# AfternoonCape_RevA1_TImux.net
KiCad netlist of a schematic drawn in Altium Designer
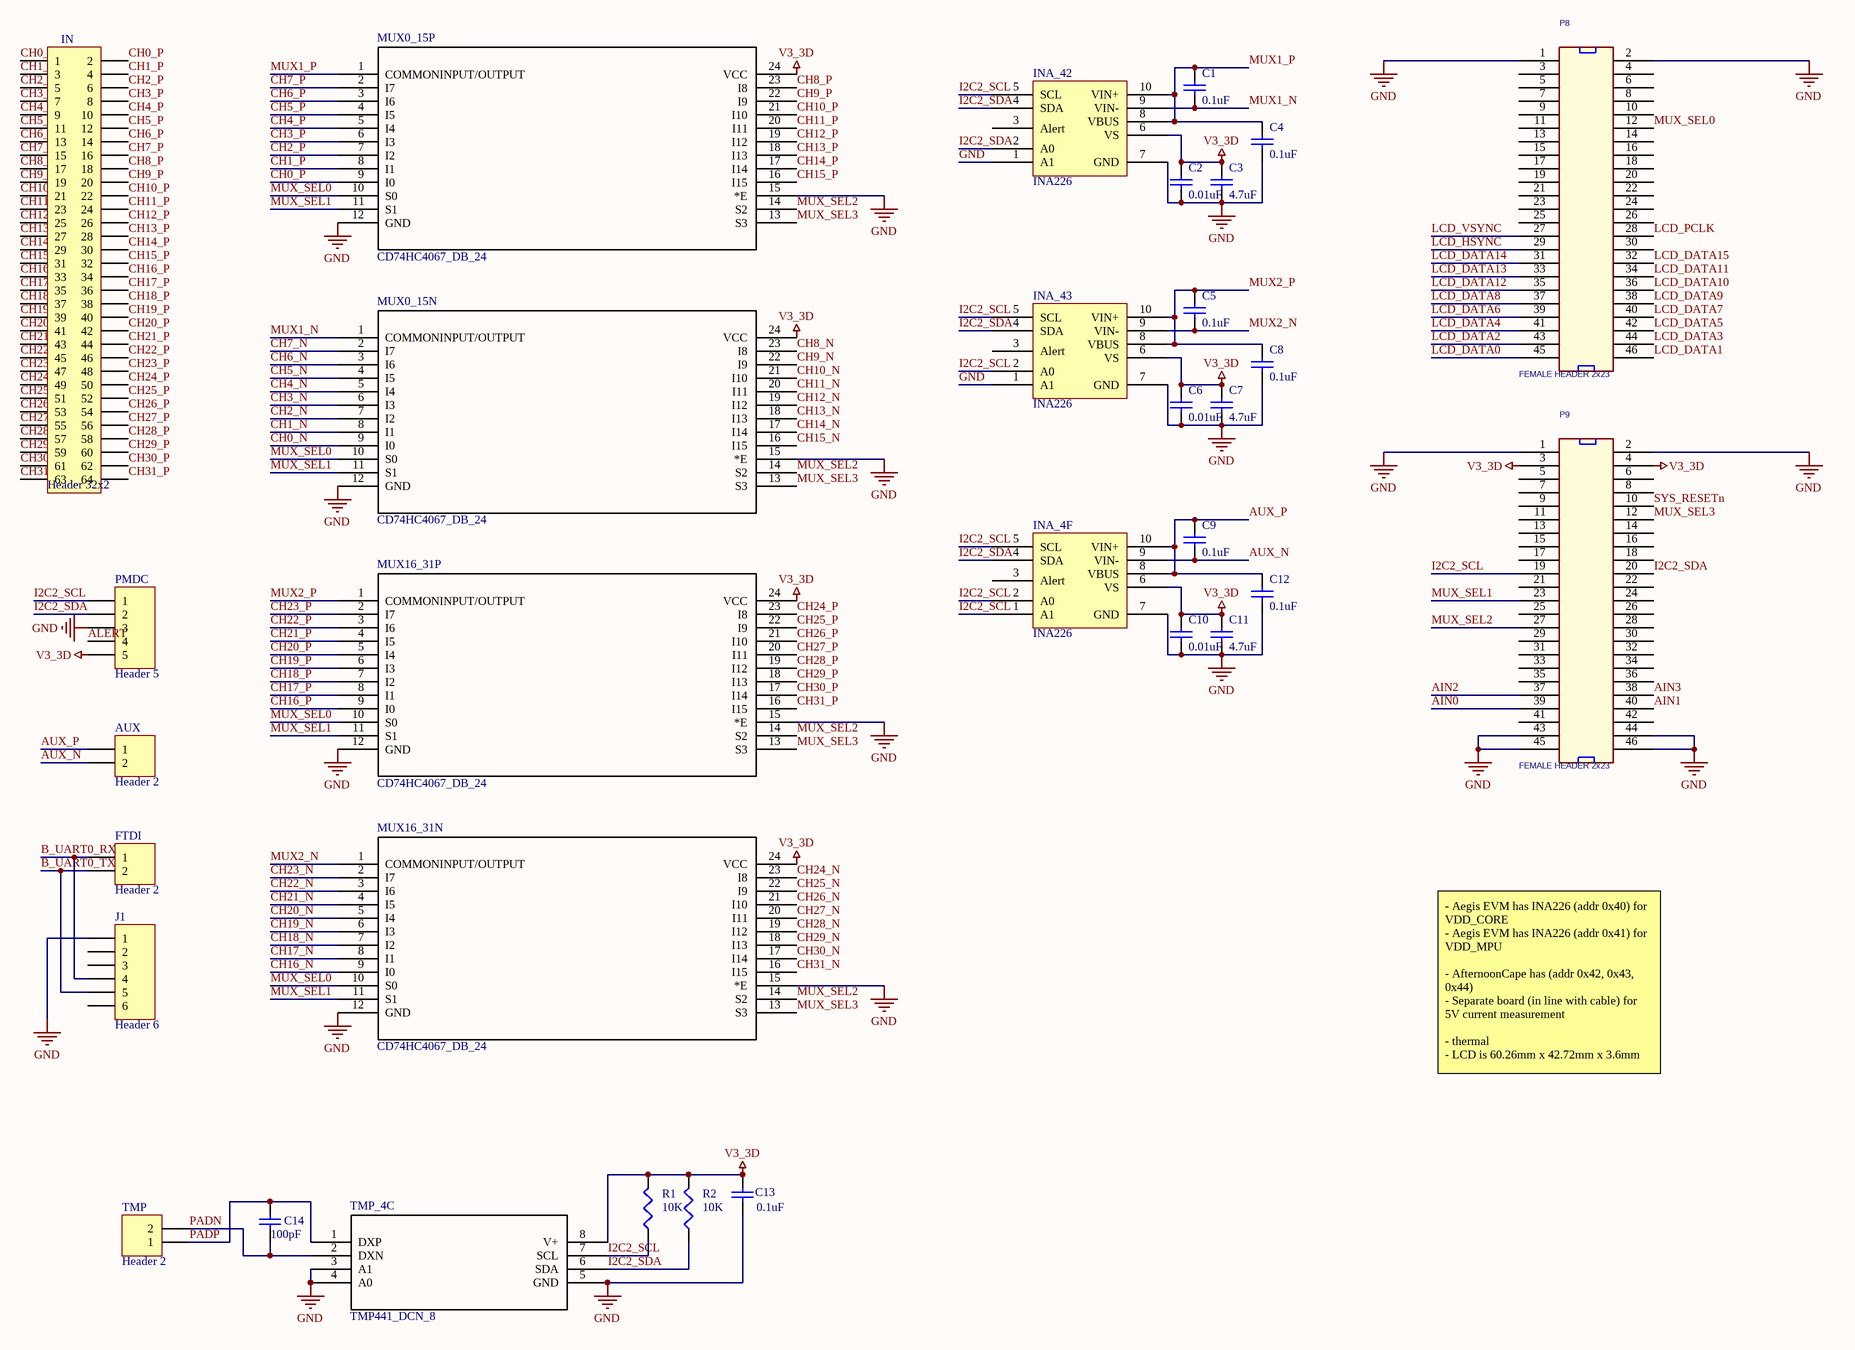
[diagram p0: AfternoonCape_RevA1_TImux.SchDoc]

(export (version "E")
  (design (tool "Eeschema 10.0.6"))
  (components
    (comp (ref "AUX")
      (value "Header 2")
      (footprint "HDR1X2")
      (description "Header, 2-Pin")
      (fields (field (name "PUBLISHER") "Altium Limited"))
      (libsource (lib "Miscellaneous Connectors") (part "Header 2"))
    )
    (comp (ref "C1")
      (value "0.1uF")
      (footprint "0402")
      (description "Capacitor (Semiconductor SIM Model)")
      (fields (field (name "Comment") "Cap Semi") (field (name "PUBLISHER") "Altium Limited"))
      (libsource (lib "Miscellaneous Devices") (part "Cap Semi"))
    )
    (comp (ref "C2")
      (value "0.01uF")
      (footprint "0402")
      (description "Capacitor (Semiconductor SIM Model)")
      (fields (field (name "Comment") "Cap Semi") (field (name "PUBLISHER") "Altium Limited"))
      (libsource (lib "Miscellaneous Devices") (part "Cap Semi"))
    )
    (comp (ref "C3")
      (value "4.7uF")
      (footprint "0402")
      (description "Capacitor (Semiconductor SIM Model)")
      (fields (field (name "Comment") "Cap Semi") (field (name "PUBLISHER") "Altium Limited"))
      (libsource (lib "Miscellaneous Devices") (part "Cap Semi"))
    )
    (comp (ref "C4")
      (value "0.1uF")
      (footprint "0402")
      (description "Capacitor (Semiconductor SIM Model)")
      (fields (field (name "Comment") "Cap Semi") (field (name "PUBLISHER") "Altium Limited"))
      (libsource (lib "Miscellaneous Devices") (part "Cap Semi"))
    )
    (comp (ref "C5")
      (value "0.1uF")
      (footprint "0402")
      (description "Capacitor (Semiconductor SIM Model)")
      (fields (field (name "Comment") "Cap Semi") (field (name "PUBLISHER") "Altium Limited"))
      (libsource (lib "Miscellaneous Devices") (part "Cap Semi"))
    )
    (comp (ref "C6")
      (value "0.01uF")
      (footprint "0402")
      (description "Capacitor (Semiconductor SIM Model)")
      (fields (field (name "Comment") "Cap Semi") (field (name "PUBLISHER") "Altium Limited"))
      (libsource (lib "Miscellaneous Devices") (part "Cap Semi"))
    )
    (comp (ref "C7")
      (value "4.7uF")
      (footprint "0402")
      (description "Capacitor (Semiconductor SIM Model)")
      (fields (field (name "Comment") "Cap Semi") (field (name "PUBLISHER") "Altium Limited"))
      (libsource (lib "Miscellaneous Devices") (part "Cap Semi"))
    )
    (comp (ref "C8")
      (value "0.1uF")
      (footprint "0402")
      (description "Capacitor (Semiconductor SIM Model)")
      (fields (field (name "Comment") "Cap Semi") (field (name "PUBLISHER") "Altium Limited"))
      (libsource (lib "Miscellaneous Devices") (part "Cap Semi"))
    )
    (comp (ref "C9")
      (value "0.1uF")
      (footprint "0402")
      (description "Capacitor (Semiconductor SIM Model)")
      (fields (field (name "Comment") "Cap Semi") (field (name "PUBLISHER") "Altium Limited"))
      (libsource (lib "Miscellaneous Devices") (part "Cap Semi"))
    )
    (comp (ref "C10")
      (value "0.01uF")
      (footprint "0402")
      (description "Capacitor (Semiconductor SIM Model)")
      (fields (field (name "Comment") "Cap Semi") (field (name "PUBLISHER") "Altium Limited"))
      (libsource (lib "Miscellaneous Devices") (part "Cap Semi"))
    )
    (comp (ref "C11")
      (value "4.7uF")
      (footprint "0402")
      (description "Capacitor (Semiconductor SIM Model)")
      (fields (field (name "Comment") "Cap Semi") (field (name "PUBLISHER") "Altium Limited"))
      (libsource (lib "Miscellaneous Devices") (part "Cap Semi"))
    )
    (comp (ref "C12")
      (value "0.1uF")
      (footprint "0402")
      (description "Capacitor (Semiconductor SIM Model)")
      (fields (field (name "Comment") "Cap Semi") (field (name "PUBLISHER") "Altium Limited"))
      (libsource (lib "Miscellaneous Devices") (part "Cap Semi"))
    )
    (comp (ref "C13")
      (value "0.1uF")
      (footprint "0402")
      (description "Capacitor (Semiconductor SIM Model)")
      (fields (field (name "Comment") "Cap Semi") (field (name "PUBLISHER") "Altium Limited"))
      (libsource (lib "Miscellaneous Devices") (part "Cap Semi"))
    )
    (comp (ref "C14")
      (value "100pF")
      (footprint "0402")
      (description "Capacitor (Semiconductor SIM Model)")
      (fields (field (name "Comment") "Cap Semi") (field (name "PUBLISHER") "Altium Limited"))
      (libsource (lib "Miscellaneous Devices") (part "Cap Semi"))
    )
    (comp (ref "FTDI")
      (value "Header 2")
      (footprint "HDR1X2")
      (description "Header, 2-Pin")
      (fields (field (name "PUBLISHER") "Altium Limited"))
      (libsource (lib "Miscellaneous Connectors") (part "Header 2"))
    )
    (comp (ref "IN")
      (value "Header 32x2")
      (footprint "HDR2x32")
      (description "Header, 32-Pin, Dual row")
      (libsource (lib "Miscellaneous Connectors") (part "Header 32x2"))
    )
    (comp (ref "INA_4F") (value "INA226") (footprint "DGS10") (libsource (lib "INA226") (part "INA226")))
    (comp (ref "INA_42") (value "INA226") (footprint "DGS10") (libsource (lib "INA226") (part "INA226")))
    (comp (ref "INA_43") (value "INA226") (footprint "DGS10") (libsource (lib "INA226") (part "INA226")))
    (comp (ref "J1")
      (value "Header 6")
      (footprint "HDR1X6")
      (description "6-pin female header, long legs for FTDI-USB cable")
      (fields (field (name "PUBLISHER") "Altium Limited"))
      (libsource (lib "Miscellaneous Connectors") (part "Header 6"))
    )
    (comp (ref "MUX0_15N")
      (value "CD74HC4067_DB_24")
      (footprint "DB24")
      (description "Imported")
      (fields
        (field (name "MANUFACTURER") "Texas Instruments")
        (field (name "GENERIC_PART_NUMBER") "CD74HC4067")
      )
      (libsource (lib "CD74HC4067_DB") (part "CD74HC4067_DB_24"))
    )
    (comp (ref "MUX0_15P")
      (value "CD74HC4067_DB_24")
      (footprint "DB24")
      (description "Imported")
      (fields
        (field (name "MANUFACTURER") "Texas Instruments")
        (field (name "GENERIC_PART_NUMBER") "CD74HC4067")
      )
      (libsource (lib "CD74HC4067_DB") (part "CD74HC4067_DB_24"))
    )
    (comp (ref "MUX16_31N")
      (value "CD74HC4067_DB_24")
      (footprint "DB24")
      (description "Imported")
      (fields
        (field (name "MANUFACTURER") "Texas Instruments")
        (field (name "GENERIC_PART_NUMBER") "CD74HC4067")
      )
      (libsource (lib "CD74HC4067_DB") (part "CD74HC4067_DB_24"))
    )
    (comp (ref "MUX16_31P")
      (value "CD74HC4067_DB_24")
      (footprint "DB24")
      (description "Imported")
      (fields
        (field (name "MANUFACTURER") "Texas Instruments")
        (field (name "GENERIC_PART_NUMBER") "CD74HC4067")
      )
      (libsource (lib "CD74HC4067_DB") (part "CD74HC4067_DB_24"))
    )
    (comp (ref "P8")
      (value "FEMALE HEADER 2x23")
      (description "CONN HEADER FMAL 46PS.1\" DL GOLD")
      (fields
        (field (name "MANUFACTURER") "Sullins Connector Solutions")
        (field (name "MANUFACTURER PART NUMBER") "PPPC232LFBN-RC")
      )
      (libsource (lib "BEAGLEBONEBLACK_REV A5B") (part "HDR_46_F_2_0.1_0.1"))
    )
    (comp (ref "P9")
      (value "FEMALE HEADER 2x23")
      (description "CONN HEADER FMAL 46PS.1\" DL GOLD")
      (fields
        (field (name "MANUFACTURER") "Sullins Connector Solutions")
        (field (name "MANUFACTURER PART NUMBER") "PPPC232LFBN-RC")
      )
      (libsource (lib "BEAGLEBONEBLACK_REV A5B") (part "HDR_46_F_2_0.1_0.1"))
    )
    (comp (ref "PMDC")
      (value "Header 5")
      (footprint "HDR1X5")
      (description "Header, 5-Pin")
      (fields (field (name "PUBLISHER") "Altium Limited"))
      (libsource (lib "Miscellaneous Connectors") (part "Header 5"))
    )
    (comp (ref "R1")
      (value "10K")
      (footprint "0402")
      (description "Resistor")
      (fields (field (name "Comment") "Res3") (field (name "PUBLISHER") "Altium Limited"))
      (libsource (lib "Miscellaneous Devices") (part "Res3"))
    )
    (comp (ref "R2")
      (value "10K")
      (footprint "0402")
      (description "Resistor")
      (fields (field (name "Comment") "Res3") (field (name "PUBLISHER") "Altium Limited"))
      (libsource (lib "Miscellaneous Devices") (part "Res3"))
    )
    (comp (ref "TMP")
      (value "Header 2")
      (footprint "HDR1X2")
      (description "Header, 2-Pin")
      (fields (field (name "PUBLISHER") "Altium Limited"))
      (libsource (lib "") (part "Header 2_1"))
    )
    (comp (ref "TMP_4C")
      (value "TMP441_DCN_8")
      (footprint "TMP441:DCN8-L")
      (description "Imported")
      (fields
        (field (name "MANUFACTURER_PART_NUMBER") "tmp441_dcn_8")
        (field (name "GENERIC_PART_NUMBER") "TMP441")
      )
      (libsource (lib "TMP441") (part "TMP441_DCN_8"))
    )
  )
  (nets
    (net (code "1") (name "/AIN0") (class "Default")
      (node (ref "P9") (pin "39") (pinfunction "20_39") (pintype "passive"))
    )
    (net (code "2") (name "/AIN1") (class "Default")
      (node (ref "P9") (pin "40") (pinfunction "45_40") (pintype "passive"))
    )
    (net (code "3") (name "/AIN2") (class "Default")
      (node (ref "P9") (pin "37") (pinfunction "19_37") (pintype "passive"))
    )
    (net (code "4") (name "/AIN3") (class "Default")
      (node (ref "P9") (pin "38") (pinfunction "44_38") (pintype "passive"))
    )
    (net (code "5") (name "/ALERT") (class "Default")
      (node (ref "PMDC") (pin "4") (pinfunction "4_4") (pintype "passive"))
    )
    (net (code "6") (name "/AUX_N") (class "Default")
      (node (ref "AUX") (pin "2") (pinfunction "2_2") (pintype "passive"))
      (node (ref "C9") (pin "1") (pinfunction "1_1") (pintype "passive"))
      (node (ref "INA_4F") (pin "9") (pinfunction "VIN-_9") (pintype "passive"))
    )
    (net (code "7") (name "/AUX_P") (class "Default")
      (node (ref "AUX") (pin "1") (pinfunction "1_1") (pintype "passive"))
      (node (ref "C12") (pin "2") (pinfunction "2_2") (pintype "passive"))
      (node (ref "C9") (pin "2") (pinfunction "2_2") (pintype "passive"))
      (node (ref "INA_4F") (pin "10") (pinfunction "VIN+_10") (pintype "passive"))
      (node (ref "INA_4F") (pin "8") (pinfunction "VBUS_8") (pintype "passive"))
    )
    (net (code "8") (name "/B_UART0_RX") (class "Default")
      (node (ref "FTDI") (pin "1") (pinfunction "1_1") (pintype "passive"))
      (node (ref "J1") (pin "4") (pinfunction "4_4") (pintype "passive"))
    )
    (net (code "9") (name "/B_UART0_TX") (class "Default")
      (node (ref "FTDI") (pin "2") (pinfunction "2_2") (pintype "passive"))
      (node (ref "J1") (pin "5") (pinfunction "5_5") (pintype "passive"))
    )
    (net (code "10") (name "/CH0_N") (class "Default")
      (node (ref "IN") (pin "1") (pinfunction "1_1") (pintype "passive"))
      (node (ref "MUX0_15N") (pin "9") (pinfunction "I0_9") (pintype "passive"))
    )
    (net (code "11") (name "/CH0_P") (class "Default")
      (node (ref "IN") (pin "2") (pinfunction "2_2") (pintype "passive"))
      (node (ref "MUX0_15P") (pin "9") (pinfunction "I0_9") (pintype "passive"))
    )
    (net (code "12") (name "/CH1_N") (class "Default")
      (node (ref "IN") (pin "3") (pinfunction "3_3") (pintype "passive"))
      (node (ref "MUX0_15N") (pin "8") (pinfunction "I1_8") (pintype "passive"))
    )
    (net (code "13") (name "/CH1_P") (class "Default")
      (node (ref "IN") (pin "4") (pinfunction "4_4") (pintype "passive"))
      (node (ref "MUX0_15P") (pin "8") (pinfunction "I1_8") (pintype "passive"))
    )
    (net (code "14") (name "/CH2_N") (class "Default")
      (node (ref "IN") (pin "5") (pinfunction "5_5") (pintype "passive"))
      (node (ref "MUX0_15N") (pin "7") (pinfunction "I2_7") (pintype "passive"))
    )
    (net (code "15") (name "/CH2_P") (class "Default")
      (node (ref "IN") (pin "6") (pinfunction "6_6") (pintype "passive"))
      (node (ref "MUX0_15P") (pin "7") (pinfunction "I2_7") (pintype "passive"))
    )
    (net (code "16") (name "/CH3_N") (class "Default")
      (node (ref "IN") (pin "7") (pinfunction "7_7") (pintype "passive"))
      (node (ref "MUX0_15N") (pin "6") (pinfunction "I3_6") (pintype "passive"))
    )
    (net (code "17") (name "/CH3_P") (class "Default")
      (node (ref "IN") (pin "8") (pinfunction "8_8") (pintype "passive"))
      (node (ref "MUX0_15P") (pin "6") (pinfunction "I3_6") (pintype "passive"))
    )
    (net (code "18") (name "/CH4_N") (class "Default")
      (node (ref "IN") (pin "9") (pinfunction "9_9") (pintype "passive"))
      (node (ref "MUX0_15N") (pin "5") (pinfunction "I4_5") (pintype "passive"))
    )
    (net (code "19") (name "/CH4_P") (class "Default")
      (node (ref "IN") (pin "10") (pinfunction "10_10") (pintype "passive"))
      (node (ref "MUX0_15P") (pin "5") (pinfunction "I4_5") (pintype "passive"))
    )
    (net (code "20") (name "/CH5_N") (class "Default")
      (node (ref "IN") (pin "11") (pinfunction "11_11") (pintype "passive"))
      (node (ref "MUX0_15N") (pin "4") (pinfunction "I5_4") (pintype "passive"))
    )
    (net (code "21") (name "/CH5_P") (class "Default")
      (node (ref "IN") (pin "12") (pinfunction "12_12") (pintype "passive"))
      (node (ref "MUX0_15P") (pin "4") (pinfunction "I5_4") (pintype "passive"))
    )
    (net (code "22") (name "/CH6_N") (class "Default")
      (node (ref "IN") (pin "13") (pinfunction "13_13") (pintype "passive"))
      (node (ref "MUX0_15N") (pin "3") (pinfunction "I6_3") (pintype "passive"))
    )
    (net (code "23") (name "/CH6_P") (class "Default")
      (node (ref "IN") (pin "14") (pinfunction "14_14") (pintype "passive"))
      (node (ref "MUX0_15P") (pin "3") (pinfunction "I6_3") (pintype "passive"))
    )
    (net (code "24") (name "/CH7_N") (class "Default")
      (node (ref "IN") (pin "15") (pinfunction "15_15") (pintype "passive"))
      (node (ref "MUX0_15N") (pin "2") (pinfunction "I7_2") (pintype "passive"))
    )
    (net (code "25") (name "/CH7_P") (class "Default")
      (node (ref "IN") (pin "16") (pinfunction "16_16") (pintype "passive"))
      (node (ref "MUX0_15P") (pin "2") (pinfunction "I7_2") (pintype "passive"))
    )
    (net (code "26") (name "/CH8_N") (class "Default")
      (node (ref "IN") (pin "17") (pinfunction "17_17") (pintype "passive"))
      (node (ref "MUX0_15N") (pin "23") (pinfunction "I8_23") (pintype "passive"))
    )
    (net (code "27") (name "/CH8_P") (class "Default")
      (node (ref "IN") (pin "18") (pinfunction "18_18") (pintype "passive"))
      (node (ref "MUX0_15P") (pin "23") (pinfunction "I8_23") (pintype "passive"))
    )
    (net (code "28") (name "/CH9_N") (class "Default")
      (node (ref "IN") (pin "19") (pinfunction "19_19") (pintype "passive"))
      (node (ref "MUX0_15N") (pin "22") (pinfunction "I9_22") (pintype "passive"))
    )
    (net (code "29") (name "/CH9_P") (class "Default")
      (node (ref "IN") (pin "20") (pinfunction "20_20") (pintype "passive"))
      (node (ref "MUX0_15P") (pin "22") (pinfunction "I9_22") (pintype "passive"))
    )
    (net (code "30") (name "/CH10_N") (class "Default")
      (node (ref "IN") (pin "21") (pinfunction "21_21") (pintype "passive"))
      (node (ref "MUX0_15N") (pin "21") (pinfunction "I10_21") (pintype "passive"))
    )
    (net (code "31") (name "/CH10_P") (class "Default")
      (node (ref "IN") (pin "22") (pinfunction "22_22") (pintype "passive"))
      (node (ref "MUX0_15P") (pin "21") (pinfunction "I10_21") (pintype "passive"))
    )
    (net (code "32") (name "/CH11_N") (class "Default")
      (node (ref "IN") (pin "23") (pinfunction "23_23") (pintype "passive"))
      (node (ref "MUX0_15N") (pin "20") (pinfunction "I11_20") (pintype "passive"))
    )
    (net (code "33") (name "/CH11_P") (class "Default")
      (node (ref "IN") (pin "24") (pinfunction "24_24") (pintype "passive"))
      (node (ref "MUX0_15P") (pin "20") (pinfunction "I11_20") (pintype "passive"))
    )
    (net (code "34") (name "/CH12_N") (class "Default")
      (node (ref "IN") (pin "25") (pinfunction "25_25") (pintype "passive"))
      (node (ref "MUX0_15N") (pin "19") (pinfunction "I12_19") (pintype "passive"))
    )
    (net (code "35") (name "/CH12_P") (class "Default")
      (node (ref "IN") (pin "26") (pinfunction "26_26") (pintype "passive"))
      (node (ref "MUX0_15P") (pin "19") (pinfunction "I12_19") (pintype "passive"))
    )
    (net (code "36") (name "/CH13_N") (class "Default")
      (node (ref "IN") (pin "27") (pinfunction "27_27") (pintype "passive"))
      (node (ref "MUX0_15N") (pin "18") (pinfunction "I13_18") (pintype "passive"))
    )
    (net (code "37") (name "/CH13_P") (class "Default")
      (node (ref "IN") (pin "28") (pinfunction "28_28") (pintype "passive"))
      (node (ref "MUX0_15P") (pin "18") (pinfunction "I13_18") (pintype "passive"))
    )
    (net (code "38") (name "/CH14_N") (class "Default")
      (node (ref "IN") (pin "29") (pinfunction "29_29") (pintype "passive"))
      (node (ref "MUX0_15N") (pin "17") (pinfunction "I14_17") (pintype "passive"))
    )
    (net (code "39") (name "/CH14_P") (class "Default")
      (node (ref "IN") (pin "30") (pinfunction "30_30") (pintype "passive"))
      (node (ref "MUX0_15P") (pin "17") (pinfunction "I14_17") (pintype "passive"))
    )
    (net (code "40") (name "/CH15_N") (class "Default")
      (node (ref "IN") (pin "31") (pinfunction "31_31") (pintype "passive"))
      (node (ref "MUX0_15N") (pin "16") (pinfunction "I15_16") (pintype "passive"))
    )
    (net (code "41") (name "/CH15_P") (class "Default")
      (node (ref "IN") (pin "32") (pinfunction "32_32") (pintype "passive"))
      (node (ref "MUX0_15P") (pin "16") (pinfunction "I15_16") (pintype "passive"))
    )
    (net (code "42") (name "/CH16_N") (class "Default")
      (node (ref "IN") (pin "33") (pinfunction "33_33") (pintype "passive"))
      (node (ref "MUX16_31N") (pin "9") (pinfunction "I0_9") (pintype "passive"))
    )
    (net (code "43") (name "/CH16_P") (class "Default")
      (node (ref "IN") (pin "34") (pinfunction "34_34") (pintype "passive"))
      (node (ref "MUX16_31P") (pin "9") (pinfunction "I0_9") (pintype "passive"))
    )
    (net (code "44") (name "/CH17_N") (class "Default")
      (node (ref "IN") (pin "35") (pinfunction "35_35") (pintype "passive"))
      (node (ref "MUX16_31N") (pin "8") (pinfunction "I1_8") (pintype "passive"))
    )
    (net (code "45") (name "/CH17_P") (class "Default")
      (node (ref "IN") (pin "36") (pinfunction "36_36") (pintype "passive"))
      (node (ref "MUX16_31P") (pin "8") (pinfunction "I1_8") (pintype "passive"))
    )
    (net (code "46") (name "/CH18_N") (class "Default")
      (node (ref "IN") (pin "37") (pinfunction "37_37") (pintype "passive"))
      (node (ref "MUX16_31N") (pin "7") (pinfunction "I2_7") (pintype "passive"))
    )
    (net (code "47") (name "/CH18_P") (class "Default")
      (node (ref "IN") (pin "38") (pinfunction "38_38") (pintype "passive"))
      (node (ref "MUX16_31P") (pin "7") (pinfunction "I2_7") (pintype "passive"))
    )
    (net (code "48") (name "/CH19_N") (class "Default")
      (node (ref "IN") (pin "39") (pinfunction "39_39") (pintype "passive"))
      (node (ref "MUX16_31N") (pin "6") (pinfunction "I3_6") (pintype "passive"))
    )
    (net (code "49") (name "/CH19_P") (class "Default")
      (node (ref "IN") (pin "40") (pinfunction "40_40") (pintype "passive"))
      (node (ref "MUX16_31P") (pin "6") (pinfunction "I3_6") (pintype "passive"))
    )
    (net (code "50") (name "/CH20_N") (class "Default")
      (node (ref "IN") (pin "41") (pinfunction "41_41") (pintype "passive"))
      (node (ref "MUX16_31N") (pin "5") (pinfunction "I4_5") (pintype "passive"))
    )
    (net (code "51") (name "/CH20_P") (class "Default")
      (node (ref "IN") (pin "42") (pinfunction "42_42") (pintype "passive"))
      (node (ref "MUX16_31P") (pin "5") (pinfunction "I4_5") (pintype "passive"))
    )
    (net (code "52") (name "/CH21_N") (class "Default")
      (node (ref "IN") (pin "43") (pinfunction "43_43") (pintype "passive"))
      (node (ref "MUX16_31N") (pin "4") (pinfunction "I5_4") (pintype "passive"))
    )
    (net (code "53") (name "/CH21_P") (class "Default")
      (node (ref "IN") (pin "44") (pinfunction "44_44") (pintype "passive"))
      (node (ref "MUX16_31P") (pin "4") (pinfunction "I5_4") (pintype "passive"))
    )
    (net (code "54") (name "/CH22_N") (class "Default")
      (node (ref "IN") (pin "45") (pinfunction "45_45") (pintype "passive"))
      (node (ref "MUX16_31N") (pin "3") (pinfunction "I6_3") (pintype "passive"))
    )
    (net (code "55") (name "/CH22_P") (class "Default")
      (node (ref "IN") (pin "46") (pinfunction "46_46") (pintype "passive"))
      (node (ref "MUX16_31P") (pin "3") (pinfunction "I6_3") (pintype "passive"))
    )
    (net (code "56") (name "/CH23_N") (class "Default")
      (node (ref "IN") (pin "47") (pinfunction "47_47") (pintype "passive"))
      (node (ref "MUX16_31N") (pin "2") (pinfunction "I7_2") (pintype "passive"))
    )
    (net (code "57") (name "/CH23_P") (class "Default")
      (node (ref "IN") (pin "48") (pinfunction "48_48") (pintype "passive"))
      (node (ref "MUX16_31P") (pin "2") (pinfunction "I7_2") (pintype "passive"))
    )
    (net (code "58") (name "/CH24_N") (class "Default")
      (node (ref "IN") (pin "49") (pinfunction "49_49") (pintype "passive"))
      (node (ref "MUX16_31N") (pin "23") (pinfunction "I8_23") (pintype "passive"))
    )
    (net (code "59") (name "/CH24_P") (class "Default")
      (node (ref "IN") (pin "50") (pinfunction "50_50") (pintype "passive"))
      (node (ref "MUX16_31P") (pin "23") (pinfunction "I8_23") (pintype "passive"))
    )
    (net (code "60") (name "/CH25_N") (class "Default")
      (node (ref "IN") (pin "51") (pinfunction "51_51") (pintype "passive"))
      (node (ref "MUX16_31N") (pin "22") (pinfunction "I9_22") (pintype "passive"))
    )
    (net (code "61") (name "/CH25_P") (class "Default")
      (node (ref "IN") (pin "52") (pinfunction "52_52") (pintype "passive"))
      (node (ref "MUX16_31P") (pin "22") (pinfunction "I9_22") (pintype "passive"))
    )
    (net (code "62") (name "/CH26_N") (class "Default")
      (node (ref "IN") (pin "53") (pinfunction "53_53") (pintype "passive"))
      (node (ref "MUX16_31N") (pin "21") (pinfunction "I10_21") (pintype "passive"))
    )
    (net (code "63") (name "/CH26_P") (class "Default")
      (node (ref "IN") (pin "54") (pinfunction "54_54") (pintype "passive"))
      (node (ref "MUX16_31P") (pin "21") (pinfunction "I10_21") (pintype "passive"))
    )
    (net (code "64") (name "/CH27_N") (class "Default")
      (node (ref "IN") (pin "55") (pinfunction "55_55") (pintype "passive"))
      (node (ref "MUX16_31N") (pin "20") (pinfunction "I11_20") (pintype "passive"))
    )
    (net (code "65") (name "/CH27_P") (class "Default")
      (node (ref "IN") (pin "56") (pinfunction "56_56") (pintype "passive"))
      (node (ref "MUX16_31P") (pin "20") (pinfunction "I11_20") (pintype "passive"))
    )
    (net (code "66") (name "/CH28_N") (class "Default")
      (node (ref "IN") (pin "57") (pinfunction "57_57") (pintype "passive"))
      (node (ref "MUX16_31N") (pin "19") (pinfunction "I12_19") (pintype "passive"))
    )
    (net (code "67") (name "/CH28_P") (class "Default")
      (node (ref "IN") (pin "58") (pinfunction "58_58") (pintype "passive"))
      (node (ref "MUX16_31P") (pin "19") (pinfunction "I12_19") (pintype "passive"))
    )
    (net (code "68") (name "/CH29_N") (class "Default")
      (node (ref "IN") (pin "59") (pinfunction "59_59") (pintype "passive"))
      (node (ref "MUX16_31N") (pin "18") (pinfunction "I13_18") (pintype "passive"))
    )
    (net (code "69") (name "/CH29_P") (class "Default")
      (node (ref "IN") (pin "60") (pinfunction "60_60") (pintype "passive"))
      (node (ref "MUX16_31P") (pin "18") (pinfunction "I13_18") (pintype "passive"))
    )
    (net (code "70") (name "/CH30_N") (class "Default")
      (node (ref "IN") (pin "61") (pinfunction "61_61") (pintype "passive"))
      (node (ref "MUX16_31N") (pin "17") (pinfunction "I14_17") (pintype "passive"))
    )
    (net (code "71") (name "/CH30_P") (class "Default")
      (node (ref "IN") (pin "62") (pinfunction "62_62") (pintype "passive"))
      (node (ref "MUX16_31P") (pin "17") (pinfunction "I14_17") (pintype "passive"))
    )
    (net (code "72") (name "/CH31_N") (class "Default")
      (node (ref "IN") (pin "63") (pinfunction "63_63") (pintype "passive"))
      (node (ref "MUX16_31N") (pin "16") (pinfunction "I15_16") (pintype "passive"))
    )
    (net (code "73") (name "/CH31_P") (class "Default")
      (node (ref "IN") (pin "64") (pinfunction "64_64") (pintype "passive"))
      (node (ref "MUX16_31P") (pin "16") (pinfunction "I15_16") (pintype "passive"))
    )
    (net (code "74") (name "/I2C2_SCL") (class "Default")
      (node (ref "INA_42") (pin "5") (pinfunction "SCL_5") (pintype "passive"))
      (node (ref "INA_43") (pin "2") (pinfunction "A0_2") (pintype "passive"))
      (node (ref "INA_43") (pin "5") (pinfunction "SCL_5") (pintype "passive"))
      (node (ref "INA_4F") (pin "1") (pinfunction "A1_1") (pintype "passive"))
      (node (ref "INA_4F") (pin "2") (pinfunction "A0_2") (pintype "passive"))
      (node (ref "INA_4F") (pin "5") (pinfunction "SCL_5") (pintype "passive"))
      (node (ref "P9") (pin "19") (pinfunction "10_19") (pintype "passive"))
      (node (ref "PMDC") (pin "1") (pinfunction "1_1") (pintype "passive"))
      (node (ref "R1") (pin "1") (pinfunction "1_1") (pintype "passive"))
      (node (ref "TMP_4C") (pin "7") (pinfunction "SCL_7") (pintype "passive"))
    )
    (net (code "75") (name "/I2C2_SDA") (class "Default")
      (node (ref "INA_42") (pin "2") (pinfunction "A0_2") (pintype "passive"))
      (node (ref "INA_42") (pin "4") (pinfunction "SDA_4") (pintype "passive"))
      (node (ref "INA_43") (pin "4") (pinfunction "SDA_4") (pintype "passive"))
      (node (ref "INA_4F") (pin "4") (pinfunction "SDA_4") (pintype "passive"))
      (node (ref "P9") (pin "20") (pinfunction "35_20") (pintype "passive"))
      (node (ref "PMDC") (pin "2") (pinfunction "2_2") (pintype "passive"))
      (node (ref "R2") (pin "1") (pinfunction "1_1") (pintype "passive"))
      (node (ref "TMP_4C") (pin "6") (pinfunction "SDA_6") (pintype "passive"))
    )
    (net (code "76") (name "/LCD_DATA0") (class "Default")
      (node (ref "P8") (pin "45") (pinfunction "23_45") (pintype "passive"))
    )
    (net (code "77") (name "/LCD_DATA1") (class "Default")
      (node (ref "P8") (pin "46") (pinfunction "48_46") (pintype "passive"))
    )
    (net (code "78") (name "/LCD_DATA2") (class "Default")
      (node (ref "P8") (pin "43") (pinfunction "22_43") (pintype "passive"))
    )
    (net (code "79") (name "/LCD_DATA3") (class "Default")
      (node (ref "P8") (pin "44") (pinfunction "47_44") (pintype "passive"))
    )
    (net (code "80") (name "/LCD_DATA4") (class "Default")
      (node (ref "P8") (pin "41") (pinfunction "21_41") (pintype "passive"))
    )
    (net (code "81") (name "/LCD_DATA5") (class "Default")
      (node (ref "P8") (pin "42") (pinfunction "46_42") (pintype "passive"))
    )
    (net (code "82") (name "/LCD_DATA6") (class "Default")
      (node (ref "P8") (pin "39") (pinfunction "20_39") (pintype "passive"))
    )
    (net (code "83") (name "/LCD_DATA7") (class "Default")
      (node (ref "P8") (pin "40") (pinfunction "45_40") (pintype "passive"))
    )
    (net (code "84") (name "/LCD_DATA8") (class "Default")
      (node (ref "P8") (pin "37") (pinfunction "19_37") (pintype "passive"))
    )
    (net (code "85") (name "/LCD_DATA9") (class "Default")
      (node (ref "P8") (pin "38") (pinfunction "44_38") (pintype "passive"))
    )
    (net (code "86") (name "/LCD_DATA10") (class "Default")
      (node (ref "P8") (pin "36") (pinfunction "43_36") (pintype "passive"))
    )
    (net (code "87") (name "/LCD_DATA11") (class "Default")
      (node (ref "P8") (pin "34") (pinfunction "42_34") (pintype "passive"))
    )
    (net (code "88") (name "/LCD_DATA12") (class "Default")
      (node (ref "P8") (pin "35") (pinfunction "18_35") (pintype "passive"))
    )
    (net (code "89") (name "/LCD_DATA13") (class "Default")
      (node (ref "P8") (pin "33") (pinfunction "17_33") (pintype "passive"))
    )
    (net (code "90") (name "/LCD_DATA14") (class "Default")
      (node (ref "P8") (pin "31") (pinfunction "16_31") (pintype "passive"))
    )
    (net (code "91") (name "/LCD_DATA15") (class "Default")
      (node (ref "P8") (pin "32") (pinfunction "41_32") (pintype "passive"))
    )
    (net (code "92") (name "/LCD_HSYNC") (class "Default")
      (node (ref "P8") (pin "29") (pinfunction "15_29") (pintype "passive"))
    )
    (net (code "93") (name "/LCD_PCLK") (class "Default")
      (node (ref "P8") (pin "28") (pinfunction "39_28") (pintype "passive"))
    )
    (net (code "94") (name "/LCD_VSYNC") (class "Default")
      (node (ref "P8") (pin "27") (pinfunction "14_27") (pintype "passive"))
    )
    (net (code "95") (name "/MUX1_N") (class "Default")
      (node (ref "C1") (pin "1") (pinfunction "1_1") (pintype "passive"))
      (node (ref "INA_42") (pin "9") (pinfunction "VIN-_9") (pintype "passive"))
      (node (ref "MUX0_15N") (pin "1") (pinfunction "COMMONINPUT/OUTPUT_1") (pintype "passive"))
    )
    (net (code "96") (name "/MUX1_P") (class "Default")
      (node (ref "C1") (pin "2") (pinfunction "2_2") (pintype "passive"))
      (node (ref "C4") (pin "2") (pinfunction "2_2") (pintype "passive"))
      (node (ref "INA_42") (pin "10") (pinfunction "VIN+_10") (pintype "passive"))
      (node (ref "INA_42") (pin "8") (pinfunction "VBUS_8") (pintype "passive"))
      (node (ref "MUX0_15P") (pin "1") (pinfunction "COMMONINPUT/OUTPUT_1") (pintype "passive"))
    )
    (net (code "97") (name "/MUX2_N") (class "Default")
      (node (ref "C5") (pin "1") (pinfunction "1_1") (pintype "passive"))
      (node (ref "INA_43") (pin "9") (pinfunction "VIN-_9") (pintype "passive"))
      (node (ref "MUX16_31N") (pin "1") (pinfunction "COMMONINPUT/OUTPUT_1") (pintype "passive"))
    )
    (net (code "98") (name "/MUX2_P") (class "Default")
      (node (ref "C5") (pin "2") (pinfunction "2_2") (pintype "passive"))
      (node (ref "C8") (pin "2") (pinfunction "2_2") (pintype "passive"))
      (node (ref "INA_43") (pin "10") (pinfunction "VIN+_10") (pintype "passive"))
      (node (ref "INA_43") (pin "8") (pinfunction "VBUS_8") (pintype "passive"))
      (node (ref "MUX16_31P") (pin "1") (pinfunction "COMMONINPUT/OUTPUT_1") (pintype "passive"))
    )
    (net (code "99") (name "/MUX_SEL0") (class "Default")
      (node (ref "MUX0_15N") (pin "10") (pinfunction "S0_10") (pintype "passive"))
      (node (ref "MUX0_15P") (pin "10") (pinfunction "S0_10") (pintype "passive"))
      (node (ref "MUX16_31N") (pin "10") (pinfunction "S0_10") (pintype "passive"))
      (node (ref "MUX16_31P") (pin "10") (pinfunction "S0_10") (pintype "passive"))
      (node (ref "P8") (pin "12") (pinfunction "31_12") (pintype "passive"))
    )
    (net (code "100") (name "/MUX_SEL1") (class "Default")
      (node (ref "MUX0_15N") (pin "11") (pinfunction "S1_11") (pintype "passive"))
      (node (ref "MUX0_15P") (pin "11") (pinfunction "S1_11") (pintype "passive"))
      (node (ref "MUX16_31N") (pin "11") (pinfunction "S1_11") (pintype "passive"))
      (node (ref "MUX16_31P") (pin "11") (pinfunction "S1_11") (pintype "passive"))
      (node (ref "P9") (pin "23") (pinfunction "12_23") (pintype "passive"))
    )
    (net (code "101") (name "/MUX_SEL2") (class "Default")
      (node (ref "MUX0_15N") (pin "14") (pinfunction "S2_14") (pintype "passive"))
      (node (ref "MUX0_15P") (pin "14") (pinfunction "S2_14") (pintype "passive"))
      (node (ref "MUX16_31N") (pin "14") (pinfunction "S2_14") (pintype "passive"))
      (node (ref "MUX16_31P") (pin "14") (pinfunction "S2_14") (pintype "passive"))
      (node (ref "P9") (pin "27") (pinfunction "14_27") (pintype "passive"))
    )
    (net (code "102") (name "/MUX_SEL3") (class "Default")
      (node (ref "MUX0_15N") (pin "13") (pinfunction "S3_13") (pintype "passive"))
      (node (ref "MUX0_15P") (pin "13") (pinfunction "S3_13") (pintype "passive"))
      (node (ref "MUX16_31N") (pin "13") (pinfunction "S3_13") (pintype "passive"))
      (node (ref "MUX16_31P") (pin "13") (pinfunction "S3_13") (pintype "passive"))
      (node (ref "P9") (pin "12") (pinfunction "31_12") (pintype "passive"))
    )
    (net (code "103") (name "/PADN") (class "Default")
      (node (ref "C14") (pin "1") (pinfunction "1_1") (pintype "passive"))
      (node (ref "TMP") (pin "2") (pinfunction "2_2") (pintype "passive"))
      (node (ref "TMP_4C") (pin "2") (pinfunction "DXN_2") (pintype "passive"))
    )
    (net (code "104") (name "/PADP") (class "Default")
      (node (ref "C14") (pin "2") (pinfunction "2_2") (pintype "passive"))
      (node (ref "TMP") (pin "1") (pinfunction "1_1") (pintype "passive"))
      (node (ref "TMP_4C") (pin "1") (pinfunction "DXP_1") (pintype "passive"))
    )
    (net (code "105") (name "/SYS_RESETn") (class "Default")
      (node (ref "P9") (pin "10") (pinfunction "30_10") (pintype "passive"))
    )
    (net (code "106") (name "GND") (class "Default")
      (node (ref "C10") (pin "1") (pinfunction "1_1") (pintype "passive"))
      (node (ref "C11") (pin "1") (pinfunction "1_1") (pintype "passive"))
      (node (ref "C12") (pin "1") (pinfunction "1_1") (pintype "passive"))
      (node (ref "C13") (pin "1") (pinfunction "1_1") (pintype "passive"))
      (node (ref "C2") (pin "1") (pinfunction "1_1") (pintype "passive"))
      (node (ref "C3") (pin "1") (pinfunction "1_1") (pintype "passive"))
      (node (ref "C4") (pin "1") (pinfunction "1_1") (pintype "passive"))
      (node (ref "C6") (pin "1") (pinfunction "1_1") (pintype "passive"))
      (node (ref "C7") (pin "1") (pinfunction "1_1") (pintype "passive"))
      (node (ref "C8") (pin "1") (pinfunction "1_1") (pintype "passive"))
      (node (ref "INA_42") (pin "1") (pinfunction "A1_1") (pintype "passive"))
      (node (ref "INA_42") (pin "7") (pinfunction "GND_7") (pintype "passive"))
      (node (ref "INA_43") (pin "1") (pinfunction "A1_1") (pintype "passive"))
      (node (ref "INA_43") (pin "7") (pinfunction "GND_7") (pintype "passive"))
      (node (ref "INA_4F") (pin "7") (pinfunction "GND_7") (pintype "passive"))
      (node (ref "J1") (pin "1") (pinfunction "1_1") (pintype "passive"))
      (node (ref "MUX0_15N") (pin "12") (pinfunction "GND_12") (pintype "passive"))
      (node (ref "MUX0_15N") (pin "15") (pinfunction "*E_15") (pintype "passive"))
      (node (ref "MUX0_15P") (pin "12") (pinfunction "GND_12") (pintype "passive"))
      (node (ref "MUX0_15P") (pin "15") (pinfunction "*E_15") (pintype "passive"))
      (node (ref "MUX16_31N") (pin "12") (pinfunction "GND_12") (pintype "passive"))
      (node (ref "MUX16_31N") (pin "15") (pinfunction "*E_15") (pintype "passive"))
      (node (ref "MUX16_31P") (pin "12") (pinfunction "GND_12") (pintype "passive"))
      (node (ref "MUX16_31P") (pin "15") (pinfunction "*E_15") (pintype "passive"))
      (node (ref "P8") (pin "1") (pinfunction "1_1") (pintype "passive"))
      (node (ref "P8") (pin "2") (pinfunction "26_2") (pintype "passive"))
      (node (ref "P9") (pin "1") (pinfunction "1_1") (pintype "passive"))
      (node (ref "P9") (pin "2") (pinfunction "26_2") (pintype "passive"))
      (node (ref "P9") (pin "43") (pinfunction "22_43") (pintype "passive"))
      (node (ref "P9") (pin "44") (pinfunction "47_44") (pintype "passive"))
      (node (ref "P9") (pin "45") (pinfunction "23_45") (pintype "passive"))
      (node (ref "P9") (pin "46") (pinfunction "48_46") (pintype "passive"))
      (node (ref "PMDC") (pin "3") (pinfunction "3_3") (pintype "passive"))
      (node (ref "TMP_4C") (pin "3") (pinfunction "A1_3") (pintype "passive"))
      (node (ref "TMP_4C") (pin "4") (pinfunction "A0_4") (pintype "passive"))
      (node (ref "TMP_4C") (pin "5") (pinfunction "GND_5") (pintype "power_in"))
    )
    (net (code "107") (name "V3_3D") (class "Default")
      (node (ref "C10") (pin "2") (pinfunction "2_2") (pintype "passive"))
      (node (ref "C11") (pin "2") (pinfunction "2_2") (pintype "passive"))
      (node (ref "C13") (pin "2") (pinfunction "2_2") (pintype "passive"))
      (node (ref "C2") (pin "2") (pinfunction "2_2") (pintype "passive"))
      (node (ref "C3") (pin "2") (pinfunction "2_2") (pintype "passive"))
      (node (ref "C6") (pin "2") (pinfunction "2_2") (pintype "passive"))
      (node (ref "C7") (pin "2") (pinfunction "2_2") (pintype "passive"))
      (node (ref "INA_42") (pin "6") (pinfunction "VS_6") (pintype "passive"))
      (node (ref "INA_43") (pin "6") (pinfunction "VS_6") (pintype "passive"))
      (node (ref "INA_4F") (pin "6") (pinfunction "VS_6") (pintype "passive"))
      (node (ref "MUX0_15N") (pin "24") (pinfunction "VCC_24") (pintype "passive"))
      (node (ref "MUX0_15P") (pin "24") (pinfunction "VCC_24") (pintype "passive"))
      (node (ref "MUX16_31N") (pin "24") (pinfunction "VCC_24") (pintype "passive"))
      (node (ref "MUX16_31P") (pin "24") (pinfunction "VCC_24") (pintype "passive"))
      (node (ref "P9") (pin "3") (pinfunction "2_3") (pintype "passive"))
      (node (ref "P9") (pin "4") (pinfunction "27_4") (pintype "passive"))
      (node (ref "PMDC") (pin "5") (pinfunction "5_5") (pintype "passive"))
      (node (ref "R1") (pin "2") (pinfunction "2_2") (pintype "passive"))
      (node (ref "R2") (pin "2") (pinfunction "2_2") (pintype "passive"))
      (node (ref "TMP_4C") (pin "8") (pinfunction "V+_8") (pintype "power_in"))
    )
    (net (code "108") (name "unconnected-(INA_4F-Alert-Pad3)") (class "Default")
      (node (ref "INA_4F") (pin "3") (pinfunction "Alert_3") (pintype "passive"))
    )
    (net (code "109") (name "unconnected-(INA_42-Alert-Pad3)") (class "Default")
      (node (ref "INA_42") (pin "3") (pinfunction "Alert_3") (pintype "passive"))
    )
    (net (code "110") (name "unconnected-(INA_43-Alert-Pad3)") (class "Default")
      (node (ref "INA_43") (pin "3") (pinfunction "Alert_3") (pintype "passive"))
    )
    (net (code "111") (name "unconnected-(J1-Pad2)") (class "Default")
      (node (ref "J1") (pin "2") (pinfunction "2_2") (pintype "passive"))
    )
    (net (code "112") (name "unconnected-(J1-Pad3)") (class "Default")
      (node (ref "J1") (pin "3") (pinfunction "3_3") (pintype "passive"))
    )
    (net (code "113") (name "unconnected-(J1-Pad6)") (class "Default")
      (node (ref "J1") (pin "6") (pinfunction "6_6") (pintype "passive"))
    )
    (net (code "114") (name "unconnected-(P8-2-Pad3)") (class "Default")
      (node (ref "P8") (pin "3") (pinfunction "2_3") (pintype "passive"))
    )
    (net (code "115") (name "unconnected-(P8-3-Pad5)") (class "Default")
      (node (ref "P8") (pin "5") (pinfunction "3_5") (pintype "passive"))
    )
    (net (code "116") (name "unconnected-(P8-4-Pad7)") (class "Default")
      (node (ref "P8") (pin "7") (pinfunction "4_7") (pintype "passive"))
    )
    (net (code "117") (name "unconnected-(P8-5-Pad9)") (class "Default")
      (node (ref "P8") (pin "9") (pinfunction "5_9") (pintype "passive"))
    )
    (net (code "118") (name "unconnected-(P8-6-Pad11)") (class "Default")
      (node (ref "P8") (pin "11") (pinfunction "6_11") (pintype "passive"))
    )
    (net (code "119") (name "unconnected-(P8-7-Pad13)") (class "Default")
      (node (ref "P8") (pin "13") (pinfunction "7_13") (pintype "passive"))
    )
    (net (code "120") (name "unconnected-(P8-8-Pad15)") (class "Default")
      (node (ref "P8") (pin "15") (pinfunction "8_15") (pintype "passive"))
    )
    (net (code "121") (name "unconnected-(P8-9-Pad17)") (class "Default")
      (node (ref "P8") (pin "17") (pinfunction "9_17") (pintype "passive"))
    )
    (net (code "122") (name "unconnected-(P8-10-Pad19)") (class "Default")
      (node (ref "P8") (pin "19") (pinfunction "10_19") (pintype "passive"))
    )
    (net (code "123") (name "unconnected-(P8-11-Pad21)") (class "Default")
      (node (ref "P8") (pin "21") (pinfunction "11_21") (pintype "passive"))
    )
    (net (code "124") (name "unconnected-(P8-12-Pad23)") (class "Default")
      (node (ref "P8") (pin "23") (pinfunction "12_23") (pintype "passive"))
    )
    (net (code "125") (name "unconnected-(P8-13-Pad25)") (class "Default")
      (node (ref "P8") (pin "25") (pinfunction "13_25") (pintype "passive"))
    )
    (net (code "126") (name "unconnected-(P8-27-Pad4)") (class "Default")
      (node (ref "P8") (pin "4") (pinfunction "27_4") (pintype "passive"))
    )
    (net (code "127") (name "unconnected-(P8-28-Pad6)") (class "Default")
      (node (ref "P8") (pin "6") (pinfunction "28_6") (pintype "passive"))
    )
    (net (code "128") (name "unconnected-(P8-29-Pad8)") (class "Default")
      (node (ref "P8") (pin "8") (pinfunction "29_8") (pintype "passive"))
    )
    (net (code "129") (name "unconnected-(P8-30-Pad10)") (class "Default")
      (node (ref "P8") (pin "10") (pinfunction "30_10") (pintype "passive"))
    )
    (net (code "130") (name "unconnected-(P8-32-Pad14)") (class "Default")
      (node (ref "P8") (pin "14") (pinfunction "32_14") (pintype "passive"))
    )
    (net (code "131") (name "unconnected-(P8-33-Pad16)") (class "Default")
      (node (ref "P8") (pin "16") (pinfunction "33_16") (pintype "passive"))
    )
    (net (code "132") (name "unconnected-(P8-34-Pad18)") (class "Default")
      (node (ref "P8") (pin "18") (pinfunction "34_18") (pintype "passive"))
    )
    (net (code "133") (name "unconnected-(P8-35-Pad20)") (class "Default")
      (node (ref "P8") (pin "20") (pinfunction "35_20") (pintype "passive"))
    )
    (net (code "134") (name "unconnected-(P8-36-Pad22)") (class "Default")
      (node (ref "P8") (pin "22") (pinfunction "36_22") (pintype "passive"))
    )
    (net (code "135") (name "unconnected-(P8-37-Pad24)") (class "Default")
      (node (ref "P8") (pin "24") (pinfunction "37_24") (pintype "passive"))
    )
    (net (code "136") (name "unconnected-(P8-38-Pad26)") (class "Default")
      (node (ref "P8") (pin "26") (pinfunction "38_26") (pintype "passive"))
    )
    (net (code "137") (name "unconnected-(P8-40-Pad30)") (class "Default")
      (node (ref "P8") (pin "30") (pinfunction "40_30") (pintype "passive"))
    )
    (net (code "138") (name "unconnected-(P9-3-Pad5)") (class "Default")
      (node (ref "P9") (pin "5") (pinfunction "3_5") (pintype "passive"))
    )
    (net (code "139") (name "unconnected-(P9-4-Pad7)") (class "Default")
      (node (ref "P9") (pin "7") (pinfunction "4_7") (pintype "passive"))
    )
    (net (code "140") (name "unconnected-(P9-5-Pad9)") (class "Default")
      (node (ref "P9") (pin "9") (pinfunction "5_9") (pintype "passive"))
    )
    (net (code "141") (name "unconnected-(P9-6-Pad11)") (class "Default")
      (node (ref "P9") (pin "11") (pinfunction "6_11") (pintype "passive"))
    )
    (net (code "142") (name "unconnected-(P9-7-Pad13)") (class "Default")
      (node (ref "P9") (pin "13") (pinfunction "7_13") (pintype "passive"))
    )
    (net (code "143") (name "unconnected-(P9-8-Pad15)") (class "Default")
      (node (ref "P9") (pin "15") (pinfunction "8_15") (pintype "passive"))
    )
    (net (code "144") (name "unconnected-(P9-9-Pad17)") (class "Default")
      (node (ref "P9") (pin "17") (pinfunction "9_17") (pintype "passive"))
    )
    (net (code "145") (name "unconnected-(P9-11-Pad21)") (class "Default")
      (node (ref "P9") (pin "21") (pinfunction "11_21") (pintype "passive"))
    )
    (net (code "146") (name "unconnected-(P9-13-Pad25)") (class "Default")
      (node (ref "P9") (pin "25") (pinfunction "13_25") (pintype "passive"))
    )
    (net (code "147") (name "unconnected-(P9-15-Pad29)") (class "Default")
      (node (ref "P9") (pin "29") (pinfunction "15_29") (pintype "passive"))
    )
    (net (code "148") (name "unconnected-(P9-16-Pad31)") (class "Default")
      (node (ref "P9") (pin "31") (pinfunction "16_31") (pintype "passive"))
    )
    (net (code "149") (name "unconnected-(P9-17-Pad33)") (class "Default")
      (node (ref "P9") (pin "33") (pinfunction "17_33") (pintype "passive"))
    )
    (net (code "150") (name "unconnected-(P9-18-Pad35)") (class "Default")
      (node (ref "P9") (pin "35") (pinfunction "18_35") (pintype "passive"))
    )
    (net (code "151") (name "unconnected-(P9-21-Pad41)") (class "Default")
      (node (ref "P9") (pin "41") (pinfunction "21_41") (pintype "passive"))
    )
    (net (code "152") (name "unconnected-(P9-28-Pad6)") (class "Default")
      (node (ref "P9") (pin "6") (pinfunction "28_6") (pintype "passive"))
    )
    (net (code "153") (name "unconnected-(P9-29-Pad8)") (class "Default")
      (node (ref "P9") (pin "8") (pinfunction "29_8") (pintype "passive"))
    )
    (net (code "154") (name "unconnected-(P9-32-Pad14)") (class "Default")
      (node (ref "P9") (pin "14") (pinfunction "32_14") (pintype "passive"))
    )
    (net (code "155") (name "unconnected-(P9-33-Pad16)") (class "Default")
      (node (ref "P9") (pin "16") (pinfunction "33_16") (pintype "passive"))
    )
    (net (code "156") (name "unconnected-(P9-34-Pad18)") (class "Default")
      (node (ref "P9") (pin "18") (pinfunction "34_18") (pintype "passive"))
    )
    (net (code "157") (name "unconnected-(P9-36-Pad22)") (class "Default")
      (node (ref "P9") (pin "22") (pinfunction "36_22") (pintype "passive"))
    )
    (net (code "158") (name "unconnected-(P9-37-Pad24)") (class "Default")
      (node (ref "P9") (pin "24") (pinfunction "37_24") (pintype "passive"))
    )
    (net (code "159") (name "unconnected-(P9-38-Pad26)") (class "Default")
      (node (ref "P9") (pin "26") (pinfunction "38_26") (pintype "passive"))
    )
    (net (code "160") (name "unconnected-(P9-39-Pad28)") (class "Default")
      (node (ref "P9") (pin "28") (pinfunction "39_28") (pintype "passive"))
    )
    (net (code "161") (name "unconnected-(P9-40-Pad30)") (class "Default")
      (node (ref "P9") (pin "30") (pinfunction "40_30") (pintype "passive"))
    )
    (net (code "162") (name "unconnected-(P9-41-Pad32)") (class "Default")
      (node (ref "P9") (pin "32") (pinfunction "41_32") (pintype "passive"))
    )
    (net (code "163") (name "unconnected-(P9-42-Pad34)") (class "Default")
      (node (ref "P9") (pin "34") (pinfunction "42_34") (pintype "passive"))
    )
    (net (code "164") (name "unconnected-(P9-43-Pad36)") (class "Default")
      (node (ref "P9") (pin "36") (pinfunction "43_36") (pintype "passive"))
    )
    (net (code "165") (name "unconnected-(P9-46-Pad42)") (class "Default")
      (node (ref "P9") (pin "42") (pinfunction "46_42") (pintype "passive"))
    )
  )
)
